# MC.net
KiCad netlist of a schematic drawn in Altium Designer
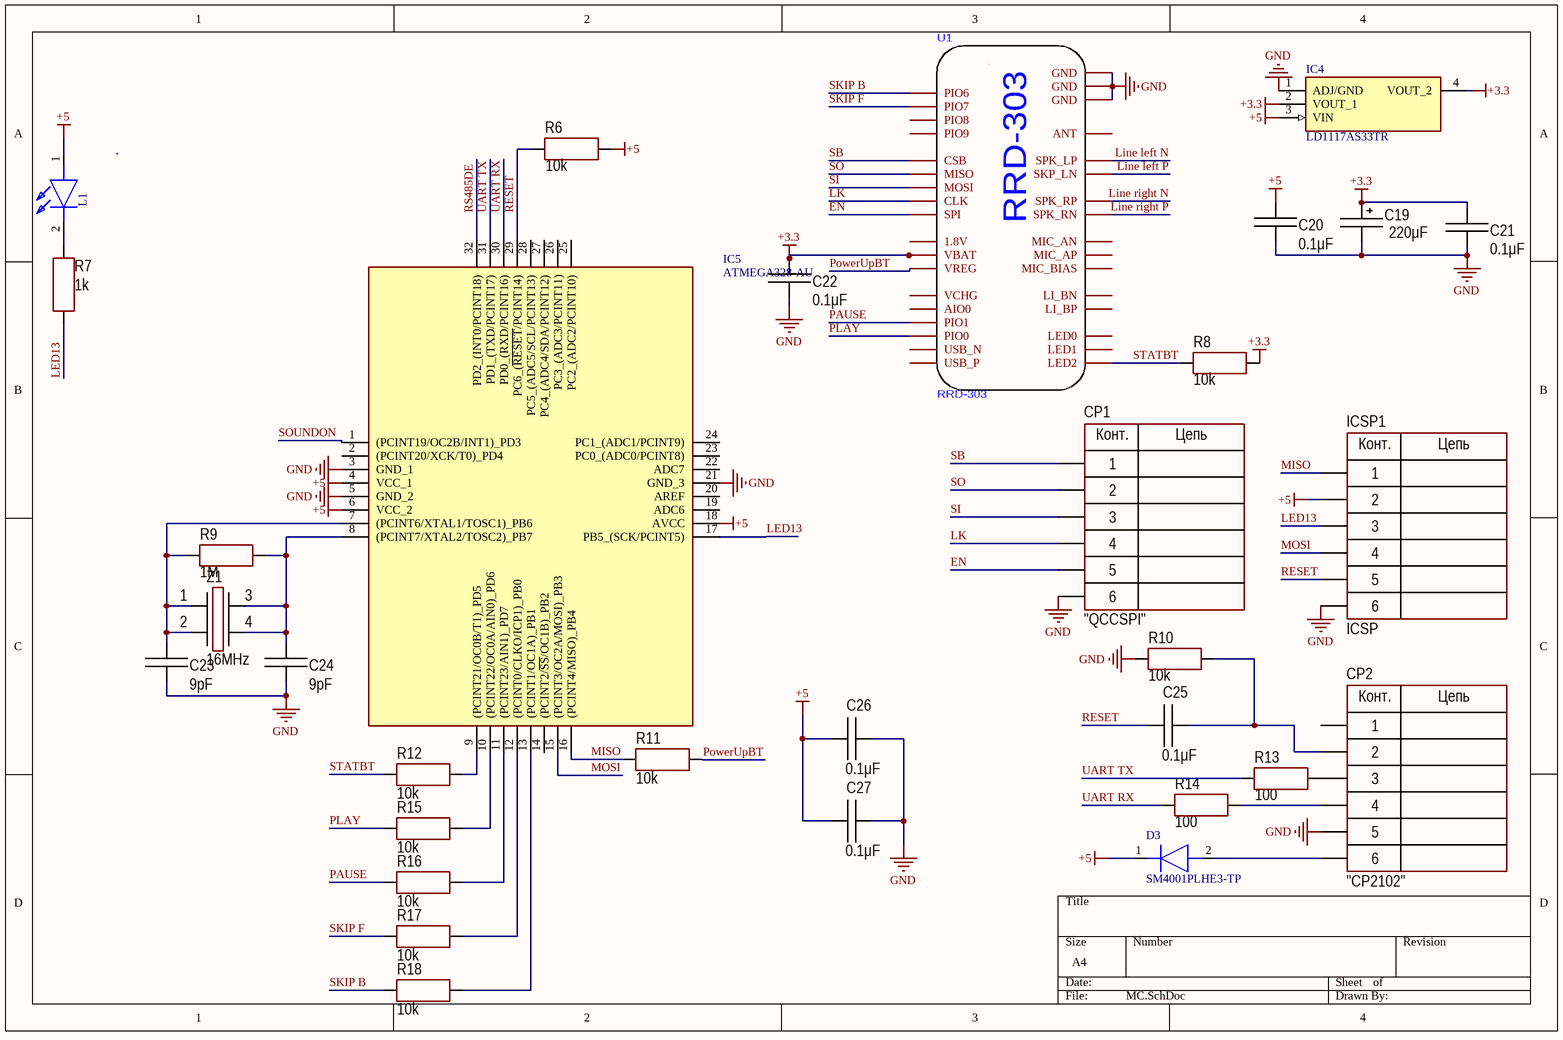
[diagram p0: MC.SchDoc]

(export (version "E")
  (design (tool "Eeschema 10.0.6"))
  (components
    (comp (ref "C19")
      (value "220μF")
      (footprint "CAP: D10C5H20")
      (fields
        (field (name "MANUFACTURER") "Wurth")
        (field (name "PARTNUMBER") "860080475013")
        (field (name "VALUEMANUFACTURERPARTNUMBER") "Aluminium capacitor, 220μF, 25V, ±20%, 54mOhm, 14x10x5 mm, -55...+105°C")
      )
      (libsource (lib "capacitor") (part "Aluminium"))
    )
    (comp (ref "C20")
      (value "0.1μF")
      (footprint "CAP: 0805")
      (fields
        (field (name "MANUFACTURER") "Yageo")
        (field (name "PARTNUMBER") "CC0805KRX7R7BB104")
        (field (name "VALUEMANUFACTURERPARTNUMBER") "Ceramic capacitor, 0.1μF, X7R, ±10%, , 0805, -55...+125°C")
      )
      (libsource (lib "capacitor") (part "Ceramic_0805"))
    )
    (comp (ref "C21")
      (value "0.1μF")
      (footprint "CAP: 0805")
      (fields
        (field (name "MANUFACTURER") "Yageo")
        (field (name "PARTNUMBER") "CC0805KRX7R7BB104")
        (field (name "VALUEMANUFACTURERPARTNUMBER") "Ceramic capacitor, 0.1μF, X7R, ±10%, , 0805, -55...+125°C")
      )
      (libsource (lib "capacitor") (part "Ceramic_0805"))
    )
    (comp (ref "C22")
      (value "0.1μF")
      (footprint "CAP: 0805")
      (fields
        (field (name "MANUFACTURER") "Yageo")
        (field (name "PARTNUMBER") "CC0805KRX7R7BB104")
        (field (name "VALUEMANUFACTURERPARTNUMBER") "Ceramic capacitor, 0.1μF, X7R, ±10%, , 0805, -55...+125°C")
      )
      (libsource (lib "capacitor") (part "Ceramic_0805"))
    )
    (comp (ref "C23")
      (value "9pF")
      (footprint "CAP: 0805")
      (fields
        (field (name "MANUFACTURER") "Yageo")
        (field (name "PARTNUMBER") "CC0805KRX7R7BB104")
        (field (name "VALUEMANUFACTURERPARTNUMBER") "Ceramic capacitor, 9pF, X7R, ±10%, , 0805, -55...+125°C")
      )
      (libsource (lib "capacitor") (part "Ceramic_0805"))
    )
    (comp (ref "C24")
      (value "9pF")
      (footprint "CAP: 0805")
      (fields
        (field (name "MANUFACTURER") "Yageo")
        (field (name "PARTNUMBER") "CC0805KRX7R7BB104")
        (field (name "VALUEMANUFACTURERPARTNUMBER") "Ceramic capacitor, 9pF, X7R, ±10%, , 0805, -55...+125°C")
      )
      (libsource (lib "capacitor") (part "Ceramic_0805"))
    )
    (comp (ref "C25")
      (value "0.1μF")
      (footprint "CAP: 0805")
      (fields
        (field (name "MANUFACTURER") "Yageo")
        (field (name "PARTNUMBER") "CC0805KRX7R7BB104")
        (field (name "VALUEMANUFACTURERPARTNUMBER") "Ceramic capacitor, 0.1μF, X7R, ±10%, , 0805, -55...+125°C")
      )
      (libsource (lib "capacitor") (part "Ceramic_0805"))
    )
    (comp (ref "C26")
      (value "0.1μF")
      (footprint "CAP: 0805")
      (fields
        (field (name "MANUFACTURER") "Yageo")
        (field (name "PARTNUMBER") "CC0805KRX7R7BB104")
        (field (name "VALUEMANUFACTURERPARTNUMBER") "Ceramic capacitor, 0.1μF, X7R, ±10%, , 0805, -55...+125°C")
      )
      (libsource (lib "capacitor") (part "Ceramic_0805"))
    )
    (comp (ref "C27")
      (value "0.1μF")
      (footprint "CAP: 0805")
      (fields
        (field (name "MANUFACTURER") "Yageo")
        (field (name "PARTNUMBER") "CC0805KRX7R7BB104")
        (field (name "VALUEMANUFACTURERPARTNUMBER") "Ceramic capacitor, 0.1μF, X7R, ±10%, , 0805, -55...+125°C")
      )
      (libsource (lib "capacitor") (part "Ceramic_0805"))
    )
    (comp (ref "CP1")
      (value "~")
      (footprint "CON: PLS-6")
      (fields
        (field (name "MANUFACTURER") "Connfly")
        (field (name "VALUEMANUFACTURERPARTNUMBER") "Connector, 6pin, 2.54mm, 500VAC, 3A")
        (field (name "PARTNUMBER") "PLS-6")
        (field (name "COMMENTTEXT") "\"QCCSPI\"")
      )
      (libsource (lib "connector") (part "PLS-6"))
    )
    (comp (ref "CP2")
      (value "~")
      (footprint "CON: PLS-6")
      (fields
        (field (name "MANUFACTURER") "Connfly")
        (field (name "VALUEMANUFACTURERPARTNUMBER") "Connector, 6pin, 2.54mm, 500VAC, 3A")
        (field (name "PARTNUMBER") "PLS-6")
        (field (name "COMMENTTEXT") "\"CP2102\"")
      )
      (libsource (lib "connector") (part "PLS-6"))
    )
    (comp (ref "D3")
      (value "SM4001PLHE3-TP")
      (footprint "SamacSys:SODFL3616X135N")
      (description "Diode")
      (fields (field (name "MOUSER PART NUMBER") "833-SM4001PLHE3-TP"))
      (libsource (lib "*") (part "SM4001PLHE3-TP"))
    )
    (comp (ref "IC4")
      (value "LD1117AS33TR")
      (footprint "SamacSys:SOT230P700X190-4N")
      (description "Power Supply")
      (fields (field (name "MOUSER PART NUMBER") "511-LD1117AS33"))
      (libsource (lib "SamacSys") (part "LD1117AS33TR"))
    )
    (comp (ref "IC5")
      (value "ATMEGA328-AU")
      (footprint "SamacSys:QFP80P900X900X120-32N")
      (description "Integrated Circuit")
      (fields (field (name "MOUSER PART NUMBER") "556-ATMEGA328-AU"))
      (libsource (lib "*") (part "ATMEGA328-AU"))
    )
    (comp (ref "ICSP1")
      (value "~")
      (footprint "CON: PBD-6")
      (fields
        (field (name "MANUFACTURER") "Connfly")
        (field (name "VALUEMANUFACTURERPARTNUMBER") "Connector, 6pin, 2.54mm, 500VAC, 3A")
        (field (name "PARTNUMBER") "PBD-6")
        (field (name "COMMENTTEXT") "ICSP")
      )
      (libsource (lib "connector") (part "PBD-6"))
    )
    (comp (ref "L1")
      (value "KP2012SGC")
      (footprint "SamacSys:KP2012SGC")
      (description "LED")
      (libsource (lib "*") (part "KP2012SGC"))
    )
    (comp (ref "R6")
      (value "10k")
      (footprint "RES: 0805")
      (fields
        (field (name "MANUFACTURER") "Yageo")
        (field (name "PARTNUMBER") "RC0805JR-07100RL")
        (field (name "VALUEMANUFACTURERPARTNUMBER") "Resistor film, 10k, ±5%, 0805, 0.125W, -55...+125°C")
      )
      (libsource (lib "resistor") (part "Resistor_0805"))
    )
    (comp (ref "R7")
      (value "1k")
      (footprint "RES: 0805")
      (fields
        (field (name "MANUFACTURER") "Yageo")
        (field (name "PARTNUMBER") "RC0805JR-07100RL")
        (field (name "VALUEMANUFACTURERPARTNUMBER") "Resistor film, 1k, ±5%, 0805, 0.125W, -55...+125°C")
      )
      (libsource (lib "") (part "Resistor_0805_1"))
    )
    (comp (ref "R8")
      (value "10k")
      (footprint "RES: 0805")
      (fields
        (field (name "MANUFACTURER") "Yageo")
        (field (name "PARTNUMBER") "RC0805JR-07100RL")
        (field (name "VALUEMANUFACTURERPARTNUMBER") "Resistor film, 10k, ±5%, 0805, 0.125W, -55...+125°C")
      )
      (libsource (lib "resistor") (part "Resistor_0805"))
    )
    (comp (ref "R9")
      (value "1M")
      (footprint "RES: 0805")
      (fields
        (field (name "MANUFACTURER") "Yageo")
        (field (name "PARTNUMBER") "RC0805JR-07100RL")
        (field (name "VALUEMANUFACTURERPARTNUMBER") "Resistor film, 1M, ±5%, 0805, 0.125W, -55...+125°C")
      )
      (libsource (lib "resistor") (part "Resistor_0805"))
    )
    (comp (ref "R10")
      (value "10k")
      (footprint "RES: 0805")
      (fields
        (field (name "MANUFACTURER") "Yageo")
        (field (name "PARTNUMBER") "RC0805JR-07100RL")
        (field (name "VALUEMANUFACTURERPARTNUMBER") "Resistor film, 10k, ±5%, 0805, 0.125W, -55...+125°C")
      )
      (libsource (lib "resistor") (part "Resistor_0805"))
    )
    (comp (ref "R11")
      (value "10k")
      (footprint "RES: 0805")
      (fields
        (field (name "MANUFACTURER") "Yageo")
        (field (name "PARTNUMBER") "RC0805JR-07100RL")
        (field (name "VALUEMANUFACTURERPARTNUMBER") "Resistor film, 10k, ±5%, 0805, 0.125W, -55...+125°C")
      )
      (libsource (lib "resistor") (part "Resistor_0805"))
    )
    (comp (ref "R12")
      (value "10k")
      (footprint "RES: 0805")
      (fields
        (field (name "MANUFACTURER") "Yageo")
        (field (name "PARTNUMBER") "RC0805JR-07100RL")
        (field (name "VALUEMANUFACTURERPARTNUMBER") "Resistor film, 10k, ±5%, 0805, 0.125W, -55...+125°C")
      )
      (libsource (lib "resistor") (part "Resistor_0805"))
    )
    (comp (ref "R13")
      (value "100")
      (footprint "RES: 0805")
      (fields
        (field (name "MANUFACTURER") "Yageo")
        (field (name "PARTNUMBER") "RC0805JR-07100RL")
        (field (name "VALUEMANUFACTURERPARTNUMBER") "Resistor film, 100, ±5%, 0805, 0.125W, -55...+125°C")
      )
      (libsource (lib "resistor") (part "Resistor_0805"))
    )
    (comp (ref "R14")
      (value "100")
      (footprint "RES: 0805")
      (fields
        (field (name "MANUFACTURER") "Yageo")
        (field (name "PARTNUMBER") "RC0805JR-07100RL")
        (field (name "VALUEMANUFACTURERPARTNUMBER") "Resistor film, 100, ±5%, 0805, 0.125W, -55...+125°C")
      )
      (libsource (lib "resistor") (part "Resistor_0805"))
    )
    (comp (ref "R15")
      (value "10k")
      (footprint "RES: 0805")
      (fields
        (field (name "MANUFACTURER") "Yageo")
        (field (name "PARTNUMBER") "RC0805JR-07100RL")
        (field (name "VALUEMANUFACTURERPARTNUMBER") "Resistor film, 10k, ±5%, 0805, 0.125W, -55...+125°C")
      )
      (libsource (lib "resistor") (part "Resistor_0805"))
    )
    (comp (ref "R16")
      (value "10k")
      (footprint "RES: 0805")
      (fields
        (field (name "MANUFACTURER") "Yageo")
        (field (name "PARTNUMBER") "RC0805JR-07100RL")
        (field (name "VALUEMANUFACTURERPARTNUMBER") "Resistor film, 10k, ±5%, 0805, 0.125W, -55...+125°C")
      )
      (libsource (lib "resistor") (part "Resistor_0805"))
    )
    (comp (ref "R17")
      (value "10k")
      (footprint "RES: 0805")
      (fields
        (field (name "MANUFACTURER") "Yageo")
        (field (name "PARTNUMBER") "RC0805JR-07100RL")
        (field (name "VALUEMANUFACTURERPARTNUMBER") "Resistor film, 10k, ±5%, 0805, 0.125W, -55...+125°C")
      )
      (libsource (lib "resistor") (part "Resistor_0805"))
    )
    (comp (ref "R18")
      (value "10k")
      (footprint "RES: 0805")
      (fields
        (field (name "MANUFACTURER") "Yageo")
        (field (name "PARTNUMBER") "RC0805JR-07100RL")
        (field (name "VALUEMANUFACTURERPARTNUMBER") "Resistor film, 10k, ±5%, 0805, 0.125W, -55...+125°C")
      )
      (libsource (lib "resistor") (part "Resistor_0805"))
    )
    (comp (ref "U1") (value "RRD-303") (footprint "RRD-303") (libsource (lib "RRD-303") (part "RRD-303")))
    (comp (ref "Z1")
      (value "~")
      (footprint "OSC: 2520")
      (fields
        (field (name "MANUFACTURER") "Epson")
        (field (name "PARTNUMBER") "FA-20H 16.0000MF20X-B")
        (field (name "VALUEMANUFACTURERPARTNUMBER") "Crystal, 16MHz, 16pF, ±20ppm, case 2520, -40...+85°C")
        (field (name "FREQUENCY") "16MHz")
      )
      (libsource (lib "oscilator") (part "Crystal_2520"))
    )
  )
  (nets
    (net (code "1") (name "+3.3") (class "Default")
      (node (ref "C19") (pin "1") (pinfunction "1_1") (pintype "passive"))
      (node (ref "C21") (pin "1") (pinfunction "1_1") (pintype "passive"))
      (node (ref "C22") (pin "1") (pinfunction "1_1") (pintype "passive"))
      (node (ref "IC4") (pin "2") (pinfunction "VOUT_1_2") (pintype "power_in"))
      (node (ref "IC4") (pin "4") (pinfunction "VOUT_2_4") (pintype "power_in"))
      (node (ref "R8") (pin "2") (pinfunction "2_2") (pintype "passive"))
      (node (ref "U1") (pin "12") (pinfunction "VBAT_12") (pintype "passive"))
    )
    (net (code "2") (name "+5") (class "Default")
      (node (ref "C20") (pin "1") (pinfunction "1_1") (pintype "passive"))
      (node (ref "C26") (pin "2") (pinfunction "2_2") (pintype "passive"))
      (node (ref "C27") (pin "2") (pinfunction "2_2") (pintype "passive"))
      (node (ref "D3") (pin "1") (pinfunction "K_1") (pintype "passive"))
      (node (ref "IC4") (pin "3") (pinfunction "VIN_3") (pintype "input"))
      (node (ref "IC5") (pin "18") (pinfunction "AVCC_18") (pintype "passive"))
      (node (ref "IC5") (pin "4") (pinfunction "VCC_1_4") (pintype "passive"))
      (node (ref "IC5") (pin "6") (pinfunction "VCC_2_6") (pintype "passive"))
      (node (ref "ICSP1") (pin "2") (pinfunction "2_2") (pintype "passive"))
      (node (ref "L1") (pin "1") (pinfunction "A_1") (pintype "passive"))
      (node (ref "R6") (pin "2") (pinfunction "2_2") (pintype "passive"))
    )
    (net (code "3") (name "/EN") (class "Default")
      (node (ref "CP1") (pin "5") (pinfunction "5_5") (pintype "power_in"))
      (node (ref "U1") (pin "10") (pinfunction "SPI_10") (pintype "passive"))
    )
    (net (code "4") (name "/LED13") (class "Default")
      (node (ref "IC5") (pin "17") (pinfunction "PB5_(SCK/PCINT5)_17") (pintype "passive"))
      (node (ref "ICSP1") (pin "3") (pinfunction "3_3") (pintype "power_in"))
      (node (ref "R7") (pin "1") (pinfunction "1_1") (pintype "passive"))
    )
    (net (code "5") (name "/LK") (class "Default")
      (node (ref "CP1") (pin "4") (pinfunction "4_4") (pintype "power_in"))
      (node (ref "U1") (pin "9") (pinfunction "CLK_9") (pintype "passive"))
    )
    (net (code "6") (name "/Line left N") (class "Default")
      (node (ref "U1") (pin "16") (pinfunction "SPK_LP_16") (pintype "passive"))
    )
    (net (code "7") (name "/Line left P") (class "Default")
      (node (ref "U1") (pin "17") (pinfunction "SKP_LN_17") (pintype "passive"))
    )
    (net (code "8") (name "/Line right N") (class "Default")
      (node (ref "U1") (pin "18") (pinfunction "SPK_RP_18") (pintype "passive"))
    )
    (net (code "9") (name "/Line right P") (class "Default")
      (node (ref "U1") (pin "19") (pinfunction "SPK_RN_19") (pintype "passive"))
    )
    (net (code "10") (name "/MISO") (class "Default")
      (node (ref "IC5") (pin "16") (pinfunction "(PCINT4/MISO)_PB4_16") (pintype "passive"))
      (node (ref "ICSP1") (pin "1") (pinfunction "1_1") (pintype "passive"))
      (node (ref "R11") (pin "1") (pinfunction "1_1") (pintype "passive"))
    )
    (net (code "11") (name "/MOSI") (class "Default")
      (node (ref "IC5") (pin "15") (pinfunction "(PCINT3/OC2A/MOSI)_PB3_15") (pintype "passive"))
      (node (ref "ICSP1") (pin "4") (pinfunction "4_4") (pintype "power_in"))
    )
    (net (code "12") (name "/PAUSE") (class "Default")
      (node (ref "R16") (pin "1") (pinfunction "1_1") (pintype "passive"))
      (node (ref "U1") (pin "30") (pinfunction "PIO1_30") (pintype "passive"))
    )
    (net (code "13") (name "/PLAY") (class "Default")
      (node (ref "R15") (pin "1") (pinfunction "1_1") (pintype "passive"))
      (node (ref "U1") (pin "31") (pinfunction "PIO0_31") (pintype "passive"))
    )
    (net (code "14") (name "/PowerUpBT") (class "Default")
      (node (ref "R11") (pin "2") (pinfunction "2_2") (pintype "passive"))
      (node (ref "U1") (pin "13") (pinfunction "VREG_13") (pintype "passive"))
    )
    (net (code "15") (name "/RESET") (class "Default")
      (node (ref "C25") (pin "2") (pinfunction "2_2") (pintype "passive"))
      (node (ref "IC5") (pin "29") (pinfunction "PC6_(~{RESET}/PCINT14)_29") (pintype "passive"))
      (node (ref "ICSP1") (pin "5") (pinfunction "5_5") (pintype "power_in"))
      (node (ref "R6") (pin "1") (pinfunction "1_1") (pintype "passive"))
    )
    (net (code "16") (name "/RS485DE") (class "Default")
      (node (ref "IC5") (pin "32") (pinfunction "PD2_(INT0/PCINT18)_32") (pintype "passive"))
    )
    (net (code "17") (name "/SB") (class "Default")
      (node (ref "CP1") (pin "1") (pinfunction "1_1") (pintype "passive"))
      (node (ref "U1") (pin "6") (pinfunction "CSB_6") (pintype "passive"))
    )
    (net (code "18") (name "/SI") (class "Default")
      (node (ref "CP1") (pin "3") (pinfunction "3_3") (pintype "power_in"))
      (node (ref "U1") (pin "8") (pinfunction "MOSI_8") (pintype "passive"))
    )
    (net (code "19") (name "/SKIP B") (class "Default")
      (node (ref "R18") (pin "1") (pinfunction "1_1") (pintype "passive"))
      (node (ref "U1") (pin "2") (pinfunction "PIO6_2") (pintype "passive"))
    )
    (net (code "20") (name "/SKIP F") (class "Default")
      (node (ref "R17") (pin "1") (pinfunction "1_1") (pintype "passive"))
      (node (ref "U1") (pin "3") (pinfunction "PIO7_3") (pintype "passive"))
    )
    (net (code "21") (name "/SO") (class "Default")
      (node (ref "CP1") (pin "2") (pinfunction "2_2") (pintype "passive"))
      (node (ref "U1") (pin "7") (pinfunction "MISO_7") (pintype "passive"))
    )
    (net (code "22") (name "/SOUNDON") (class "Default")
      (node (ref "IC5") (pin "1") (pinfunction "(PCINT19/OC2B/INT1)_PD3_1") (pintype "passive"))
    )
    (net (code "23") (name "/STATBT") (class "Default")
      (node (ref "R12") (pin "1") (pinfunction "1_1") (pintype "passive"))
      (node (ref "R8") (pin "1") (pinfunction "1_1") (pintype "passive"))
      (node (ref "U1") (pin "34") (pinfunction "LED2_34") (pintype "passive"))
    )
    (net (code "24") (name "/UART RX") (class "Default")
      (node (ref "IC5") (pin "30") (pinfunction "PD0_(RXD/PCINT16)_30") (pintype "passive"))
      (node (ref "R14") (pin "1") (pinfunction "1_1") (pintype "passive"))
    )
    (net (code "25") (name "/UART TX") (class "Default")
      (node (ref "IC5") (pin "31") (pinfunction "PD1_(TXD/PCINT17)_31") (pintype "passive"))
      (node (ref "R13") (pin "1") (pinfunction "1_1") (pintype "passive"))
    )
    (net (code "26") (name "GND") (class "Default")
      (node (ref "C19") (pin "2") (pinfunction "2_2") (pintype "passive"))
      (node (ref "C20") (pin "2") (pinfunction "2_2") (pintype "passive"))
      (node (ref "C21") (pin "2") (pinfunction "2_2") (pintype "passive"))
      (node (ref "C22") (pin "2") (pinfunction "2_2") (pintype "passive"))
      (node (ref "C23") (pin "2") (pinfunction "2_2") (pintype "passive"))
      (node (ref "C24") (pin "2") (pinfunction "2_2") (pintype "passive"))
      (node (ref "C26") (pin "1") (pinfunction "1_1") (pintype "passive"))
      (node (ref "C27") (pin "1") (pinfunction "1_1") (pintype "passive"))
      (node (ref "CP1") (pin "6") (pinfunction "6_6") (pintype "power_in"))
      (node (ref "CP2") (pin "5") (pinfunction "5_5") (pintype "power_in"))
      (node (ref "IC4") (pin "1") (pinfunction "ADJ/GND_1") (pintype "power_in"))
      (node (ref "IC5") (pin "21") (pinfunction "GND_3_21") (pintype "passive"))
      (node (ref "IC5") (pin "3") (pinfunction "GND_1_3") (pintype "passive"))
      (node (ref "IC5") (pin "5") (pinfunction "GND_2_5") (pintype "passive"))
      (node (ref "ICSP1") (pin "6") (pinfunction "6_6") (pintype "power_in"))
      (node (ref "R10") (pin "1") (pinfunction "1_1") (pintype "passive"))
      (node (ref "U1") (pin "1") (pinfunction "GND_1") (pintype "passive"))
      (node (ref "U1") (pin "15") (pinfunction "GND_15") (pintype "passive"))
      (node (ref "U1") (pin "27") (pinfunction "GND_27") (pintype "passive"))
    )
    (net (code "27") (name "Net-(C25-Pad1)") (class "Default")
      (node (ref "C25") (pin "1") (pinfunction "1_1") (pintype "passive"))
      (node (ref "CP2") (pin "2") (pinfunction "2_2") (pintype "passive"))
      (node (ref "R10") (pin "2") (pinfunction "2_2") (pintype "passive"))
    )
    (net (code "28") (name "Net-(CP2-Pad3)") (class "Default")
      (node (ref "CP2") (pin "3") (pinfunction "3_3") (pintype "power_in"))
      (node (ref "R13") (pin "2") (pinfunction "2_2") (pintype "passive"))
    )
    (net (code "29") (name "Net-(CP2-Pad4)") (class "Default")
      (node (ref "CP2") (pin "4") (pinfunction "4_4") (pintype "power_in"))
      (node (ref "R14") (pin "2") (pinfunction "2_2") (pintype "passive"))
    )
    (net (code "30") (name "Net-(D3-A)") (class "Default")
      (node (ref "CP2") (pin "6") (pinfunction "6_6") (pintype "power_in"))
      (node (ref "D3") (pin "2") (pinfunction "A_2") (pintype "passive"))
    )
    (net (code "31") (name "Net-(IC5-(PCINT0{slash}CLKO{slash}ICP1)_PB0)") (class "Default")
      (node (ref "IC5") (pin "12") (pinfunction "(PCINT0/CLKO/ICP1)_PB0_12") (pintype "passive"))
      (node (ref "R17") (pin "2") (pinfunction "2_2") (pintype "passive"))
    )
    (net (code "32") (name "Net-(IC5-(PCINT1{slash}OC1A)_PB1)") (class "Default")
      (node (ref "IC5") (pin "13") (pinfunction "(PCINT1/OC1A)_PB1_13") (pintype "passive"))
      (node (ref "R18") (pin "2") (pinfunction "2_2") (pintype "passive"))
    )
    (net (code "33") (name "Net-(IC5-(PCINT6{slash}XTAL1{slash}TOSC1)_PB6)") (class "Default")
      (node (ref "C23") (pin "1") (pinfunction "1_1") (pintype "passive"))
      (node (ref "IC5") (pin "7") (pinfunction "(PCINT6/XTAL1/TOSC1)_PB6_7") (pintype "passive"))
      (node (ref "R9") (pin "1") (pinfunction "1_1") (pintype "passive"))
      (node (ref "Z1") (pin "1") (pinfunction "1_1") (pintype "passive"))
      (node (ref "Z1") (pin "2") (pinfunction "2_2") (pintype "passive"))
    )
    (net (code "34") (name "Net-(IC5-(PCINT7{slash}XTAL2{slash}TOSC2)_PB7)") (class "Default")
      (node (ref "C24") (pin "1") (pinfunction "1_1") (pintype "passive"))
      (node (ref "IC5") (pin "8") (pinfunction "(PCINT7/XTAL2/TOSC2)_PB7_8") (pintype "passive"))
      (node (ref "R9") (pin "2") (pinfunction "2_2") (pintype "passive"))
      (node (ref "Z1") (pin "3") (pinfunction "3_3") (pintype "passive"))
      (node (ref "Z1") (pin "4") (pinfunction "4_4") (pintype "passive"))
    )
    (net (code "35") (name "Net-(IC5-(PCINT21{slash}OC0B{slash}T1)_PD5)") (class "Default")
      (node (ref "IC5") (pin "9") (pinfunction "(PCINT21/OC0B/T1)_PD5_9") (pintype "passive"))
      (node (ref "R12") (pin "2") (pinfunction "2_2") (pintype "passive"))
    )
    (net (code "36") (name "Net-(IC5-(PCINT22{slash}OC0A{slash}AIN0)_PD6)") (class "Default")
      (node (ref "IC5") (pin "10") (pinfunction "(PCINT22/OC0A/AIN0)_PD6_10") (pintype "passive"))
      (node (ref "R15") (pin "2") (pinfunction "2_2") (pintype "passive"))
    )
    (net (code "37") (name "Net-(IC5-(PCINT23{slash}AIN1)_PD7)") (class "Default")
      (node (ref "IC5") (pin "11") (pinfunction "(PCINT23/AIN1)_PD7_11") (pintype "passive"))
      (node (ref "R16") (pin "2") (pinfunction "2_2") (pintype "passive"))
    )
    (net (code "38") (name "Net-(L1-K)") (class "Default")
      (node (ref "L1") (pin "2") (pinfunction "K_2") (pintype "passive"))
      (node (ref "R7") (pin "2") (pinfunction "2_2") (pintype "passive"))
    )
    (net (code "39") (name "unconnected-(CP2-Pad1)") (class "Default")
      (node (ref "CP2") (pin "1") (pinfunction "1_1") (pintype "passive"))
    )
    (net (code "40") (name "unconnected-(IC5-(PCINT2{slash}~{SS}{slash}OC1B)_PB2-Pad14)") (class "Default")
      (node (ref "IC5") (pin "14") (pinfunction "(PCINT2/~{SS}/OC1B)_PB2_14") (pintype "passive"))
    )
    (net (code "41") (name "unconnected-(IC5-(PCINT20{slash}XCK{slash}T0)_PD4-Pad2)") (class "Default")
      (node (ref "IC5") (pin "2") (pinfunction "(PCINT20/XCK/T0)_PD4_2") (pintype "passive"))
    )
    (net (code "42") (name "unconnected-(IC5-ADC6-Pad19)") (class "Default")
      (node (ref "IC5") (pin "19") (pinfunction "ADC6_19") (pintype "passive"))
    )
    (net (code "43") (name "unconnected-(IC5-ADC7-Pad22)") (class "Default")
      (node (ref "IC5") (pin "22") (pinfunction "ADC7_22") (pintype "passive"))
    )
    (net (code "44") (name "unconnected-(IC5-AREF-Pad20)") (class "Default")
      (node (ref "IC5") (pin "20") (pinfunction "AREF_20") (pintype "passive"))
    )
    (net (code "45") (name "unconnected-(IC5-PC0_(ADC0{slash}PCINT8)-Pad23)") (class "Default")
      (node (ref "IC5") (pin "23") (pinfunction "PC0_(ADC0/PCINT8)_23") (pintype "passive"))
    )
    (net (code "46") (name "unconnected-(IC5-PC1_(ADC1{slash}PCINT9)-Pad24)") (class "Default")
      (node (ref "IC5") (pin "24") (pinfunction "PC1_(ADC1/PCINT9)_24") (pintype "passive"))
    )
    (net (code "47") (name "unconnected-(IC5-PC2_(ADC2{slash}PCINT10)-Pad25)") (class "Default")
      (node (ref "IC5") (pin "25") (pinfunction "PC2_(ADC2/PCINT10)_25") (pintype "passive"))
    )
    (net (code "48") (name "unconnected-(IC5-PC3_(ADC3{slash}PCINT11)-Pad26)") (class "Default")
      (node (ref "IC5") (pin "26") (pinfunction "PC3_(ADC3/PCINT11)_26") (pintype "passive"))
    )
    (net (code "49") (name "unconnected-(IC5-PC4_(ADC4{slash}SDA{slash}PCINT12)-Pad27)") (class "Default")
      (node (ref "IC5") (pin "27") (pinfunction "PC4_(ADC4/SDA/PCINT12)_27") (pintype "passive"))
    )
    (net (code "50") (name "unconnected-(IC5-PC5_(ADC5{slash}SCL{slash}PCINT13)-Pad28)") (class "Default")
      (node (ref "IC5") (pin "28") (pinfunction "PC5_(ADC5/SCL/PCINT13)_28") (pintype "passive"))
    )
    (net (code "51") (name "unconnected-(U1-1.8V-Pad11)") (class "Default")
      (node (ref "U1") (pin "11") (pinfunction "1.8V_11") (pintype "passive"))
    )
    (net (code "52") (name "unconnected-(U1-AIO0-Pad29)") (class "Default")
      (node (ref "U1") (pin "29") (pinfunction "AIO0_29") (pintype "passive"))
    )
    (net (code "53") (name "unconnected-(U1-ANT-Pad14)") (class "Default")
      (node (ref "U1") (pin "14") (pinfunction "ANT_14") (pintype "passive"))
    )
    (net (code "54") (name "unconnected-(U1-LED0-Pad25)") (class "Default")
      (node (ref "U1") (pin "25") (pinfunction "LED0_25") (pintype "passive"))
    )
    (net (code "55") (name "unconnected-(U1-LED1-Pad26)") (class "Default")
      (node (ref "U1") (pin "26") (pinfunction "LED1_26") (pintype "passive"))
    )
    (net (code "56") (name "unconnected-(U1-LI_BN-Pad23)") (class "Default")
      (node (ref "U1") (pin "23") (pinfunction "LI_BN_23") (pintype "passive"))
    )
    (net (code "57") (name "unconnected-(U1-LI_BP-Pad24)") (class "Default")
      (node (ref "U1") (pin "24") (pinfunction "LI_BP_24") (pintype "passive"))
    )
    (net (code "58") (name "unconnected-(U1-MIC_AN-Pad20)") (class "Default")
      (node (ref "U1") (pin "20") (pinfunction "MIC_AN_20") (pintype "passive"))
    )
    (net (code "59") (name "unconnected-(U1-MIC_AP-Pad21)") (class "Default")
      (node (ref "U1") (pin "21") (pinfunction "MIC_AP_21") (pintype "passive"))
    )
    (net (code "60") (name "unconnected-(U1-MIC_BIAS-Pad22)") (class "Default")
      (node (ref "U1") (pin "22") (pinfunction "MIC_BIAS_22") (pintype "passive"))
    )
    (net (code "61") (name "unconnected-(U1-PIO8-Pad4)") (class "Default")
      (node (ref "U1") (pin "4") (pinfunction "PIO8_4") (pintype "passive"))
    )
    (net (code "62") (name "unconnected-(U1-PIO9-Pad5)") (class "Default")
      (node (ref "U1") (pin "5") (pinfunction "PIO9_5") (pintype "passive"))
    )
    (net (code "63") (name "unconnected-(U1-USB_N-Pad32)") (class "Default")
      (node (ref "U1") (pin "32") (pinfunction "USB_N_32") (pintype "passive"))
    )
    (net (code "64") (name "unconnected-(U1-USB_P-Pad33)") (class "Default")
      (node (ref "U1") (pin "33") (pinfunction "USB_P_33") (pintype "passive"))
    )
    (net (code "65") (name "unconnected-(U1-VCHG-Pad28)") (class "Default")
      (node (ref "U1") (pin "28") (pinfunction "VCHG_28") (pintype "passive"))
    )
  )
)
